# c150_rev_c.net
KiCad netlist of a schematic drawn in EAGLE
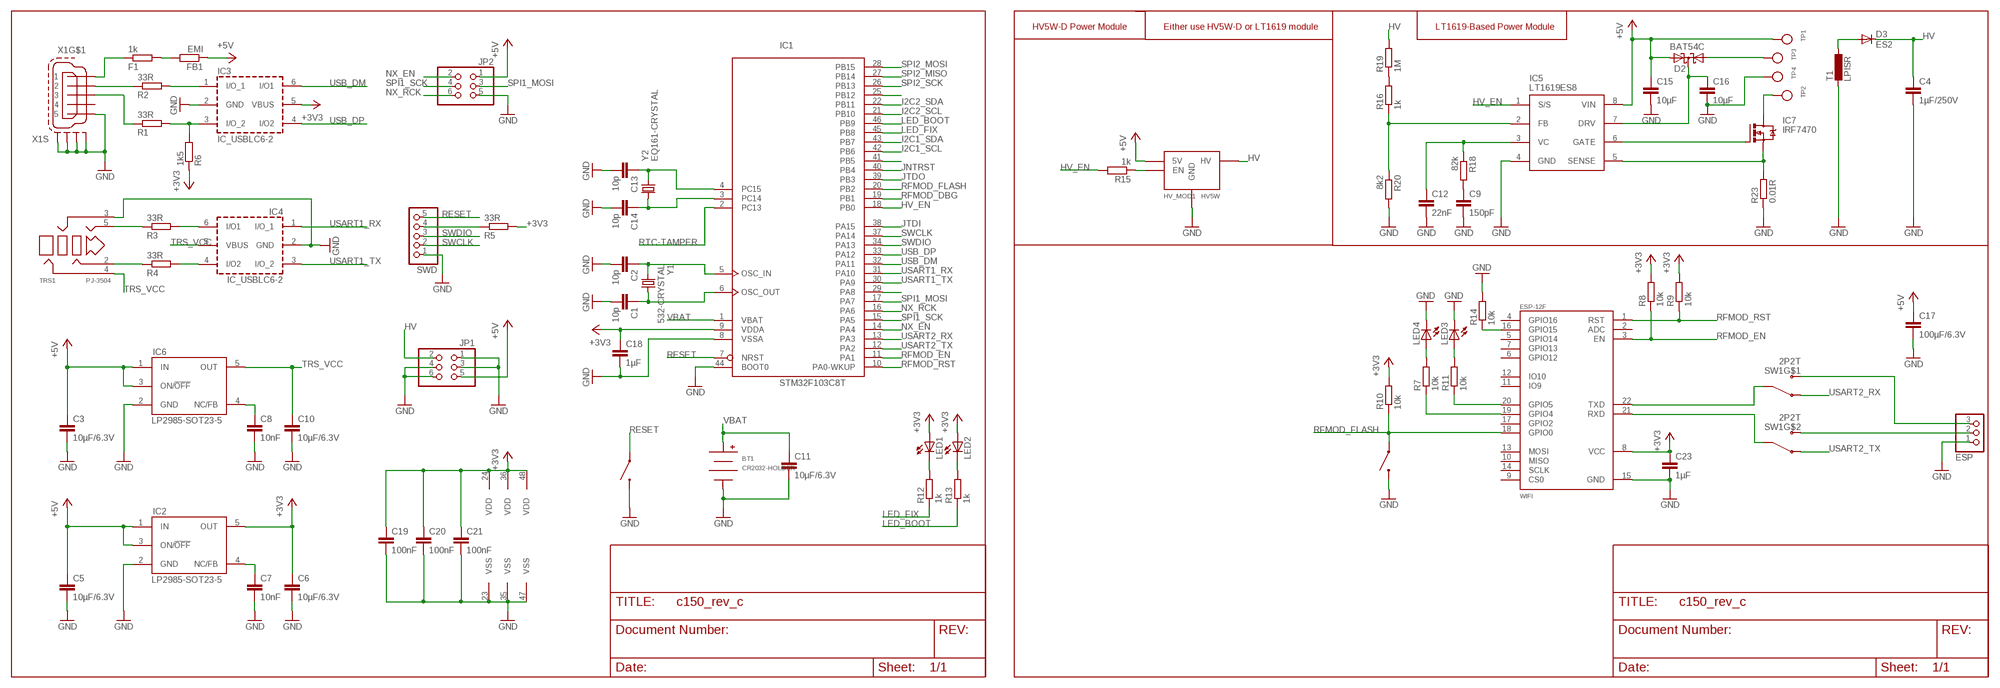
[diagram p0: schematic, sheet 1]

(export (version "E")
  (design (tool "Eeschema 10.0.6"))
  (components
    (comp (ref "BT1")
      (value "CR2032-HOLDER")
      (footprint "eagle-import:CH28-2032LF")
      (libsource (lib "eagle-import") (part "CR2032-HOLDER"))
    )
    (comp (ref "C1")
      (value "10p")
      (footprint "eagle-import:C0603")
      (libsource (lib "eagle-import") (part "C-EUC0603"))
    )
    (comp (ref "C2")
      (value "10p")
      (footprint "eagle-import:C0603")
      (libsource (lib "eagle-import") (part "C-EUC0603"))
    )
    (comp (ref "C3")
      (value "10µF/6.3V")
      (footprint "eagle-import:C0603")
      (libsource (lib "eagle-import") (part "C-EUC0603"))
    )
    (comp (ref "C4")
      (value "1µF/250V")
      (footprint "eagle-import:C2220K")
      (libsource (lib "eagle-import") (part "C-EUC2220K"))
    )
    (comp (ref "C5")
      (value "10µF/6.3V")
      (footprint "eagle-import:C0603")
      (libsource (lib "eagle-import") (part "C-EUC0603"))
    )
    (comp (ref "C6")
      (value "10µF/6.3V")
      (footprint "eagle-import:C0603")
      (libsource (lib "eagle-import") (part "C-EUC0603"))
    )
    (comp (ref "C7")
      (value "10nF")
      (footprint "eagle-import:C0603")
      (libsource (lib "eagle-import") (part "C-EUC0603"))
    )
    (comp (ref "C8")
      (value "10nF")
      (footprint "eagle-import:C0603")
      (libsource (lib "eagle-import") (part "C-EUC0603"))
    )
    (comp (ref "C9")
      (value "150pF")
      (footprint "eagle-import:C0603")
      (libsource (lib "eagle-import") (part "C-EUC0603"))
    )
    (comp (ref "C10")
      (value "10µF/6.3V")
      (footprint "eagle-import:C0603")
      (libsource (lib "eagle-import") (part "C-EUC0603"))
    )
    (comp (ref "C11")
      (value "10µF/6.3V")
      (footprint "eagle-import:C0603")
      (libsource (lib "eagle-import") (part "C-EUC0603"))
    )
    (comp (ref "C12")
      (value "22nF")
      (footprint "eagle-import:C0603")
      (libsource (lib "eagle-import") (part "C-EUC0603"))
    )
    (comp (ref "C13")
      (value "10p")
      (footprint "eagle-import:C0603")
      (libsource (lib "eagle-import") (part "C-EUC0603"))
    )
    (comp (ref "C14")
      (value "10p")
      (footprint "eagle-import:C0603")
      (libsource (lib "eagle-import") (part "C-EUC0603"))
    )
    (comp (ref "C15")
      (value "10µF")
      (footprint "eagle-import:C0603")
      (libsource (lib "eagle-import") (part "C-EUC0603"))
    )
    (comp (ref "C16")
      (value "10µF")
      (footprint "eagle-import:C0603")
      (libsource (lib "eagle-import") (part "C-EUC0603"))
    )
    (comp (ref "C17")
      (value "100µF/6.3V")
      (footprint "eagle-import:C1210")
      (libsource (lib "eagle-import") (part "C-EUC1210"))
    )
    (comp (ref "C18")
      (value "1µF")
      (footprint "eagle-import:C0603")
      (libsource (lib "eagle-import") (part "C-EUC0603"))
    )
    (comp (ref "C19")
      (value "100nF")
      (footprint "eagle-import:C0603")
      (libsource (lib "eagle-import") (part "C-EUC0603"))
    )
    (comp (ref "C20")
      (value "100nF")
      (footprint "eagle-import:C0603")
      (libsource (lib "eagle-import") (part "C-EUC0603"))
    )
    (comp (ref "C21")
      (value "100nF")
      (footprint "eagle-import:C0603")
      (libsource (lib "eagle-import") (part "C-EUC0603"))
    )
    (comp (ref "C23")
      (value "1µF")
      (footprint "eagle-import:C0603")
      (libsource (lib "eagle-import") (part "C-EUC0603"))
    )
    (comp (ref "D2")
      (value "BAT54C")
      (footprint "eagle-import:SOT23")
      (libsource (lib "eagle-import") (part "BAT54C"))
    )
    (comp (ref "D3")
      (value "ES2")
      (footprint "eagle-import:DO-214AA")
      (libsource (lib "eagle-import") (part "ES2"))
    )
    (comp (ref "ESP")
      (value "HEADER-1X3ROUND")
      (footprint "eagle-import:1X03_ROUND")
      (libsource (lib "eagle-import") (part "HEADER-1X3ROUND"))
    )
    (comp (ref "F1")
      (value "1k")
      (footprint "eagle-import:R0603")
      (libsource (lib "eagle-import") (part "R-EU_R0603"))
    )
    (comp (ref "FB1")
      (value "EMI")
      (footprint "eagle-import:R0603")
      (libsource (lib "eagle-import") (part "R-EU_R0603"))
    )
    (comp (ref "FLASH")
      (value "TACT-SWITCH-40-40")
      (footprint "eagle-import:40-40")
      (libsource (lib "eagle-import") (part "TACT-SWITCH-40-40"))
    )
    (comp (ref "HV_MOD1")
      (value "HV5W")
      (footprint "eagle-import:HV5W-D")
      (libsource (lib "eagle-import") (part "HV5W"))
    )
    (comp (ref "IC1")
      (value "STM32F103C8T")
      (footprint "eagle-import:LQFP48")
      (libsource (lib "eagle-import") (part "STM32F103CT8"))
    )
    (comp (ref "IC2")
      (value "LP2985-SOT23-5")
      (footprint "eagle-import:SOT23-5")
      (libsource (lib "eagle-import") (part "LP2985-SOT23-5"))
    )
    (comp (ref "IC3")
      (value "IC_USBLC6-2")
      (footprint "eagle-import:SOT-23-6L")
      (libsource (lib "eagle-import") (part "IC_USBLC6-2"))
    )
    (comp (ref "IC4")
      (value "IC_USBLC6-2")
      (footprint "eagle-import:SOT-23-6L")
      (libsource (lib "eagle-import") (part "IC_USBLC6-2"))
    )
    (comp (ref "IC5")
      (value "LT1619ES8")
      (footprint "eagle-import:SO8")
      (libsource (lib "eagle-import") (part "LT1619ES8"))
    )
    (comp (ref "IC6")
      (value "LP2985-SOT23-5")
      (footprint "eagle-import:SOT23-5")
      (libsource (lib "eagle-import") (part "LP2985-SOT23-5"))
    )
    (comp (ref "IC7")
      (value "IRF7470")
      (footprint "eagle-import:SO8")
      (libsource (lib "eagle-import") (part "IRF7470"))
    )
    (comp (ref "ISP")
      (value "TACT-SWITCH-40-40")
      (footprint "eagle-import:40-40")
      (libsource (lib "eagle-import") (part "TACT-SWITCH-40-40"))
    )
    (comp (ref "JP1")
      (value "PINHD-2X3_2.54-SMD")
      (footprint "eagle-import:2X03SMD")
      (libsource (lib "eagle-import") (part "PINHD-2X3_2.54-SMD"))
    )
    (comp (ref "JP2")
      (value "PINHD-2X3_2.54-SMD")
      (footprint "eagle-import:2X03SMD")
      (libsource (lib "eagle-import") (part "PINHD-2X3_2.54-SMD"))
    )
    (comp (ref "LED1")
      (value "LEDCHIP-LED0603")
      (footprint "eagle-import:CHIP-LED0603")
      (libsource (lib "eagle-import") (part "LEDCHIP-LED0603"))
    )
    (comp (ref "LED2")
      (value "LEDCHIP-LED0603")
      (footprint "eagle-import:CHIP-LED0603")
      (libsource (lib "eagle-import") (part "LEDCHIP-LED0603"))
    )
    (comp (ref "LED3")
      (value "LEDCHIP-LED0603")
      (footprint "eagle-import:CHIP-LED0603")
      (libsource (lib "eagle-import") (part "LEDCHIP-LED0603"))
    )
    (comp (ref "LED4")
      (value "LEDCHIP-LED0603")
      (footprint "eagle-import:CHIP-LED0603")
      (libsource (lib "eagle-import") (part "LEDCHIP-LED0603"))
    )
    (comp (ref "R1")
      (value "33R")
      (footprint "eagle-import:R0603")
      (libsource (lib "eagle-import") (part "R-EU_R0603"))
    )
    (comp (ref "R2")
      (value "33R")
      (footprint "eagle-import:R0603")
      (libsource (lib "eagle-import") (part "R-EU_R0603"))
    )
    (comp (ref "R3")
      (value "33R")
      (footprint "eagle-import:R0603")
      (libsource (lib "eagle-import") (part "R-EU_R0603"))
    )
    (comp (ref "R4")
      (value "33R")
      (footprint "eagle-import:R0603")
      (libsource (lib "eagle-import") (part "R-EU_R0603"))
    )
    (comp (ref "R5")
      (value "33R")
      (footprint "eagle-import:R0603")
      (libsource (lib "eagle-import") (part "R-EU_R0603"))
    )
    (comp (ref "R6")
      (value "1k5")
      (footprint "eagle-import:R0603")
      (libsource (lib "eagle-import") (part "R-EU_R0603"))
    )
    (comp (ref "R7")
      (value "10k")
      (footprint "eagle-import:R0603")
      (libsource (lib "eagle-import") (part "R-EU_R0603"))
    )
    (comp (ref "R8")
      (value "10k")
      (footprint "eagle-import:R0603")
      (libsource (lib "eagle-import") (part "R-EU_R0603"))
    )
    (comp (ref "R9")
      (value "10k")
      (footprint "eagle-import:R0603")
      (libsource (lib "eagle-import") (part "R-EU_R0603"))
    )
    (comp (ref "R10")
      (value "10k")
      (footprint "eagle-import:R0603")
      (libsource (lib "eagle-import") (part "R-EU_R0603"))
    )
    (comp (ref "R11")
      (value "10k")
      (footprint "eagle-import:R0603")
      (libsource (lib "eagle-import") (part "R-EU_R0603"))
    )
    (comp (ref "R12")
      (value "1k")
      (footprint "eagle-import:R0603")
      (libsource (lib "eagle-import") (part "R-EU_R0603"))
    )
    (comp (ref "R13")
      (value "1k")
      (footprint "eagle-import:R0603")
      (libsource (lib "eagle-import") (part "R-EU_R0603"))
    )
    (comp (ref "R14")
      (value "10k")
      (footprint "eagle-import:R0603")
      (libsource (lib "eagle-import") (part "R-EU_R0603"))
    )
    (comp (ref "R15")
      (value "1k")
      (footprint "eagle-import:R1206")
      (libsource (lib "eagle-import") (part "R-EU_R1206"))
    )
    (comp (ref "R16")
      (value "1k")
      (footprint "eagle-import:R0603")
      (libsource (lib "eagle-import") (part "R-EU_R0603"))
    )
    (comp (ref "R18")
      (value "82k")
      (footprint "eagle-import:R0603")
      (libsource (lib "eagle-import") (part "R-EU_R0603"))
    )
    (comp (ref "R19")
      (value "1M")
      (footprint "eagle-import:M1206")
      (libsource (lib "eagle-import") (part "R-EU_M1206"))
    )
    (comp (ref "R20")
      (value "8k2")
      (footprint "eagle-import:R0603")
      (libsource (lib "eagle-import") (part "R-EU_R0603"))
    )
    (comp (ref "R23")
      (value "0.01R")
      (footprint "eagle-import:R1206")
      (libsource (lib "eagle-import") (part "R-EU_R1206"))
    )
    (comp (ref "SW1")
      (value "2P2T")
      (footprint "eagle-import:MSS22D18")
      (libsource (lib "eagle-import") (part "2P2T"))
    )
    (comp (ref "SWD")
      (value "HEADER-1X5ROUND")
      (footprint "eagle-import:1X05_ROUND")
      (libsource (lib "eagle-import") (part "HEADER-1X5ROUND"))
    )
    (comp (ref "T1")
      (value "LPISR")
      (footprint "eagle-import:PISR")
      (libsource (lib "eagle-import") (part "LPISR"))
    )
    (comp (ref "TP1")
      (value "TESTPOINTROUND2MM")
      (footprint "eagle-import:TESTPOINT_ROUND_2MM")
      (libsource (lib "eagle-import") (part "TESTPOINTROUND2MM"))
    )
    (comp (ref "TP2")
      (value "TESTPOINTROUND2MM")
      (footprint "eagle-import:TESTPOINT_ROUND_2MM")
      (libsource (lib "eagle-import") (part "TESTPOINTROUND2MM"))
    )
    (comp (ref "TP3")
      (value "TESTPOINTROUND2MM")
      (footprint "eagle-import:TESTPOINT_ROUND_2MM")
      (libsource (lib "eagle-import") (part "TESTPOINTROUND2MM"))
    )
    (comp (ref "TP4")
      (value "TESTPOINTROUND2MM")
      (footprint "eagle-import:TESTPOINT_ROUND_2MM")
      (libsource (lib "eagle-import") (part "TESTPOINTROUND2MM"))
    )
    (comp (ref "TRS1")
      (value "PJ-3504")
      (footprint "eagle-import:YD-PJ-3504")
      (libsource (lib "eagle-import") (part "PJ-3504"))
    )
    (comp (ref "WIFI")
      (value "ESP-12F")
      (footprint "eagle-import:ESP-12F")
      (libsource (lib "eagle-import") (part "ESP-12F"))
    )
    (comp (ref "X1")
      (value "MINI-USB-SCHIELD-32005-201")
      (footprint "eagle-import:32005-201")
      (libsource (lib "eagle-import") (part "MINI-USB-SCHIELD-32005-201"))
    )
    (comp (ref "Y1")
      (value "532-CRYSTAL")
      (footprint "eagle-import:2PIN50X32")
      (libsource (lib "eagle-import") (part "532-CRYSTAL"))
    )
    (comp (ref "Y2")
      (value "EQ161-CRYSTAL")
      (footprint "eagle-import:EQ161")
      (libsource (lib "eagle-import") (part "EQ161-CRYSTAL"))
    )
  )
  (nets
    (net (code "1") (name "+3V3") (class "Default")
      (node (ref "C18") (pin "1") (pinfunction "1_1") (pintype "passive"))
      (node (ref "C19") (pin "1") (pinfunction "1_1") (pintype "passive"))
      (node (ref "C20") (pin "1") (pinfunction "1_1") (pintype "passive"))
      (node (ref "C21") (pin "1") (pinfunction "1_1") (pintype "passive"))
      (node (ref "C23") (pin "1") (pinfunction "1_1") (pintype "passive"))
      (node (ref "C6") (pin "1") (pinfunction "1_1") (pintype "passive"))
      (node (ref "IC1") (pin "24") (pinfunction "VDD_24") (pintype "power_in"))
      (node (ref "IC1") (pin "36") (pinfunction "VDD_36") (pintype "power_in"))
      (node (ref "IC1") (pin "48") (pinfunction "VDD_48") (pintype "power_in"))
      (node (ref "IC1") (pin "9") (pinfunction "VDDA_9") (pintype "power_in"))
      (node (ref "IC2") (pin "5") (pinfunction "OUT_5") (pintype "bidirectional"))
      (node (ref "IC3") (pin "5") (pinfunction "VBUS_5") (pintype "bidirectional"))
      (node (ref "LED1") (pin "A") (pinfunction "A_A") (pintype "passive"))
      (node (ref "LED2") (pin "A") (pinfunction "A_A") (pintype "passive"))
      (node (ref "R10") (pin "2") (pinfunction "2_2") (pintype "passive"))
      (node (ref "R5") (pin "2") (pinfunction "2_2") (pintype "passive"))
      (node (ref "R6") (pin "1") (pinfunction "1_1") (pintype "passive"))
      (node (ref "R8") (pin "2") (pinfunction "2_2") (pintype "passive"))
      (node (ref "R9") (pin "2") (pinfunction "2_2") (pintype "passive"))
      (node (ref "WIFI") (pin "8") (pinfunction "VCC_8") (pintype "bidirectional"))
    )
    (net (code "2") (name "+5V") (class "Default")
      (node (ref "C15") (pin "1") (pinfunction "1_1") (pintype "passive"))
      (node (ref "C17") (pin "1") (pinfunction "1_1") (pintype "passive"))
      (node (ref "C3") (pin "1") (pinfunction "1_1") (pintype "passive"))
      (node (ref "C5") (pin "1") (pinfunction "1_1") (pintype "passive"))
      (node (ref "D2") (pin "2") (pinfunction "A2_2") (pintype "passive"))
      (node (ref "FB1") (pin "1") (pinfunction "1_1") (pintype "passive"))
      (node (ref "HV_MOD1") (pin "+5V") (pinfunction "5V_+5V") (pintype "bidirectional"))
      (node (ref "IC2") (pin "1") (pinfunction "IN_1") (pintype "bidirectional"))
      (node (ref "IC2") (pin "3") (pinfunction "ON/~{OFF}_3") (pintype "bidirectional"))
      (node (ref "IC5") (pin "8") (pinfunction "VIN_8") (pintype "bidirectional"))
      (node (ref "IC6") (pin "1") (pinfunction "IN_1") (pintype "bidirectional"))
      (node (ref "IC6") (pin "3") (pinfunction "ON/~{OFF}_3") (pintype "bidirectional"))
      (node (ref "JP1") (pin "5") (pinfunction "5_5") (pintype "passive"))
      (node (ref "JP2") (pin "1") (pinfunction "1_1") (pintype "passive"))
      (node (ref "TP1") (pin "P$1") (pinfunction "P$1_P$1") (pintype "bidirectional"))
    )
    (net (code "3") (name "/HV") (class "Default")
      (node (ref "C4") (pin "1") (pinfunction "1_1") (pintype "passive"))
      (node (ref "D3") (pin "C") (pinfunction "C_C") (pintype "passive"))
      (node (ref "HV_MOD1") (pin "HV") (pinfunction "HV_HV") (pintype "bidirectional"))
      (node (ref "JP1") (pin "2") (pinfunction "2_2") (pintype "passive"))
      (node (ref "R19") (pin "2") (pinfunction "2_2") (pintype "passive"))
    )
    (net (code "4") (name "/HV_EN") (class "Default")
      (node (ref "IC1") (pin "18") (pinfunction "PB0_18") (pintype "bidirectional"))
      (node (ref "IC5") (pin "1") (pinfunction "S/S_1") (pintype "bidirectional"))
      (node (ref "R15") (pin "2") (pinfunction "2_2") (pintype "passive"))
    )
    (net (code "5") (name "/I2C1_SCL") (class "Default")
      (node (ref "IC1") (pin "42") (pinfunction "PB6_42") (pintype "bidirectional"))
    )
    (net (code "6") (name "/I2C1_SDA") (class "Default")
      (node (ref "IC1") (pin "43") (pinfunction "PB7_43") (pintype "bidirectional"))
    )
    (net (code "7") (name "/I2C2_SCL") (class "Default")
      (node (ref "IC1") (pin "21") (pinfunction "PB10_21") (pintype "bidirectional"))
    )
    (net (code "8") (name "/I2C2_SDA") (class "Default")
      (node (ref "IC1") (pin "22") (pinfunction "PB11_22") (pintype "bidirectional"))
    )
    (net (code "9") (name "/JNTRST") (class "Default")
      (node (ref "IC1") (pin "40") (pinfunction "PB4_40") (pintype "bidirectional"))
    )
    (net (code "10") (name "/JTDI") (class "Default")
      (node (ref "IC1") (pin "38") (pinfunction "PA15_38") (pintype "bidirectional"))
    )
    (net (code "11") (name "/JTDO") (class "Default")
      (node (ref "IC1") (pin "39") (pinfunction "PB3_39") (pintype "bidirectional"))
    )
    (net (code "12") (name "/LED_BOOT") (class "Default")
      (node (ref "IC1") (pin "46") (pinfunction "PB9_46") (pintype "bidirectional"))
      (node (ref "R13") (pin "1") (pinfunction "1_1") (pintype "passive"))
    )
    (net (code "13") (name "/LED_FIX") (class "Default")
      (node (ref "IC1") (pin "45") (pinfunction "PB8_45") (pintype "bidirectional"))
      (node (ref "R12") (pin "1") (pinfunction "1_1") (pintype "passive"))
    )
    (net (code "14") (name "/NX_EN") (class "Default")
      (node (ref "IC1") (pin "14") (pinfunction "PA4_14") (pintype "bidirectional"))
      (node (ref "JP2") (pin "2") (pinfunction "2_2") (pintype "passive"))
    )
    (net (code "15") (name "/NX_RCK") (class "Default")
      (node (ref "IC1") (pin "16") (pinfunction "PA6_16") (pintype "bidirectional"))
      (node (ref "JP2") (pin "6") (pinfunction "6_6") (pintype "passive"))
    )
    (net (code "16") (name "/RESET") (class "Default")
      (node (ref "IC1") (pin "7") (pinfunction "NRST_7") (pintype "bidirectional"))
      (node (ref "ISP") (pin "3") (pinfunction "P$2_3") (pintype "bidirectional"))
      (node (ref "ISP") (pin "4") (pinfunction "P$2_4") (pintype "bidirectional"))
      (node (ref "SWD") (pin "5") (pinfunction "5_5") (pintype "passive"))
    )
    (net (code "17") (name "/RFMOD_DBG") (class "Default")
      (node (ref "IC1") (pin "19") (pinfunction "PB1_19") (pintype "bidirectional"))
    )
    (net (code "18") (name "/RFMOD_EN") (class "Default")
      (node (ref "IC1") (pin "11") (pinfunction "PA1_11") (pintype "bidirectional"))
      (node (ref "R8") (pin "1") (pinfunction "1_1") (pintype "passive"))
      (node (ref "WIFI") (pin "3") (pinfunction "EN_3") (pintype "bidirectional"))
    )
    (net (code "19") (name "/RFMOD_FLASH") (class "Default")
      (node (ref "FLASH") (pin "3") (pinfunction "P$2_3") (pintype "bidirectional"))
      (node (ref "FLASH") (pin "4") (pinfunction "P$2_4") (pintype "bidirectional"))
      (node (ref "IC1") (pin "20") (pinfunction "PB2_20") (pintype "bidirectional"))
      (node (ref "R10") (pin "1") (pinfunction "1_1") (pintype "passive"))
      (node (ref "WIFI") (pin "18") (pinfunction "GPIO0_18") (pintype "bidirectional"))
    )
    (net (code "20") (name "/RFMOD_RST") (class "Default")
      (node (ref "IC1") (pin "10") (pinfunction "PA0-WKUP_10") (pintype "bidirectional"))
      (node (ref "R9") (pin "1") (pinfunction "1_1") (pintype "passive"))
      (node (ref "WIFI") (pin "1") (pinfunction "RST_1") (pintype "bidirectional"))
    )
    (net (code "21") (name "/RTC-TAMPER") (class "Default")
      (node (ref "IC1") (pin "2") (pinfunction "PC13_2") (pintype "bidirectional"))
    )
    (net (code "22") (name "/SPI1_MOSI") (class "Default")
      (node (ref "IC1") (pin "17") (pinfunction "PA7_17") (pintype "bidirectional"))
      (node (ref "JP2") (pin "3") (pinfunction "3_3") (pintype "passive"))
    )
    (net (code "23") (name "/SPI1_SCK") (class "Default")
      (node (ref "IC1") (pin "15") (pinfunction "PA5_15") (pintype "bidirectional"))
      (node (ref "JP2") (pin "4") (pinfunction "4_4") (pintype "passive"))
    )
    (net (code "24") (name "/SPI2_MISO") (class "Default")
      (node (ref "IC1") (pin "27") (pinfunction "PB14_27") (pintype "bidirectional"))
    )
    (net (code "25") (name "/SPI2_MOSI") (class "Default")
      (node (ref "IC1") (pin "28") (pinfunction "PB15_28") (pintype "bidirectional"))
    )
    (net (code "26") (name "/SPI2_SCK") (class "Default")
      (node (ref "IC1") (pin "26") (pinfunction "PB13_26") (pintype "bidirectional"))
    )
    (net (code "27") (name "/SWCLK") (class "Default")
      (node (ref "IC1") (pin "37") (pinfunction "PA14_37") (pintype "bidirectional"))
      (node (ref "SWD") (pin "2") (pinfunction "2_2") (pintype "passive"))
    )
    (net (code "28") (name "/SWDIO") (class "Default")
      (node (ref "IC1") (pin "34") (pinfunction "PA13_34") (pintype "bidirectional"))
      (node (ref "SWD") (pin "3") (pinfunction "3_3") (pintype "passive"))
    )
    (net (code "29") (name "/TRS_VCC") (class "Default")
      (node (ref "C10") (pin "1") (pinfunction "1_1") (pintype "passive"))
      (node (ref "IC4") (pin "5") (pinfunction "VBUS_5") (pintype "bidirectional"))
      (node (ref "IC6") (pin "5") (pinfunction "OUT_5") (pintype "bidirectional"))
      (node (ref "TRS1") (pin "4") (pinfunction "4_4") (pintype "bidirectional"))
    )
    (net (code "30") (name "/USART1_RX") (class "Default")
      (node (ref "IC1") (pin "31") (pinfunction "PA10_31") (pintype "bidirectional"))
      (node (ref "IC4") (pin "1") (pinfunction "I/O_1_1") (pintype "bidirectional"))
    )
    (net (code "31") (name "/USART1_TX") (class "Default")
      (node (ref "IC1") (pin "30") (pinfunction "PA9_30") (pintype "bidirectional"))
      (node (ref "IC4") (pin "3") (pinfunction "I/O_2_3") (pintype "bidirectional"))
    )
    (net (code "32") (name "/USART2_RX") (class "Default")
      (node (ref "IC1") (pin "13") (pinfunction "PA3_13") (pintype "bidirectional"))
      (node (ref "SW1") (pin "A1") (pinfunction "A_A1") (pintype "bidirectional"))
    )
    (net (code "33") (name "/USART2_TX") (class "Default")
      (node (ref "IC1") (pin "12") (pinfunction "PA2_12") (pintype "bidirectional"))
      (node (ref "SW1") (pin "A2") (pinfunction "A_A2") (pintype "bidirectional"))
    )
    (net (code "34") (name "/USB_DM") (class "Default")
      (node (ref "IC1") (pin "32") (pinfunction "PA11_32") (pintype "bidirectional"))
      (node (ref "IC3") (pin "6") (pinfunction "I/O1_6") (pintype "bidirectional"))
    )
    (net (code "35") (name "/USB_DP") (class "Default")
      (node (ref "IC1") (pin "33") (pinfunction "PA12_33") (pintype "bidirectional"))
      (node (ref "IC3") (pin "4") (pinfunction "I/O2_4") (pintype "bidirectional"))
    )
    (net (code "36") (name "/VBAT") (class "Default")
      (node (ref "BT1") (pin "POS") (pinfunction "POS_POS") (pintype "bidirectional"))
      (node (ref "C11") (pin "1") (pinfunction "1_1") (pintype "passive"))
      (node (ref "IC1") (pin "1") (pinfunction "VBAT_1") (pintype "power_in"))
    )
    (net (code "37") (name "GND") (class "Default")
      (node (ref "BT1") (pin "NEG") (pinfunction "NEG_NEG") (pintype "bidirectional"))
      (node (ref "C1") (pin "2") (pinfunction "2_2") (pintype "passive"))
      (node (ref "C10") (pin "2") (pinfunction "2_2") (pintype "passive"))
      (node (ref "C11") (pin "2") (pinfunction "2_2") (pintype "passive"))
      (node (ref "C12") (pin "2") (pinfunction "2_2") (pintype "passive"))
      (node (ref "C13") (pin "2") (pinfunction "2_2") (pintype "passive"))
      (node (ref "C14") (pin "2") (pinfunction "2_2") (pintype "passive"))
      (node (ref "C15") (pin "2") (pinfunction "2_2") (pintype "passive"))
      (node (ref "C16") (pin "2") (pinfunction "2_2") (pintype "passive"))
      (node (ref "C17") (pin "2") (pinfunction "2_2") (pintype "passive"))
      (node (ref "C18") (pin "2") (pinfunction "2_2") (pintype "passive"))
      (node (ref "C19") (pin "2") (pinfunction "2_2") (pintype "passive"))
      (node (ref "C2") (pin "2") (pinfunction "2_2") (pintype "passive"))
      (node (ref "C20") (pin "2") (pinfunction "2_2") (pintype "passive"))
      (node (ref "C21") (pin "2") (pinfunction "2_2") (pintype "passive"))
      (node (ref "C23") (pin "2") (pinfunction "2_2") (pintype "passive"))
      (node (ref "C3") (pin "2") (pinfunction "2_2") (pintype "passive"))
      (node (ref "C4") (pin "2") (pinfunction "2_2") (pintype "passive"))
      (node (ref "C5") (pin "2") (pinfunction "2_2") (pintype "passive"))
      (node (ref "C6") (pin "2") (pinfunction "2_2") (pintype "passive"))
      (node (ref "C7") (pin "2") (pinfunction "2_2") (pintype "passive"))
      (node (ref "C8") (pin "2") (pinfunction "2_2") (pintype "passive"))
      (node (ref "C9") (pin "2") (pinfunction "2_2") (pintype "passive"))
      (node (ref "ESP") (pin "1") (pinfunction "1_1") (pintype "passive"))
      (node (ref "FLASH") (pin "1") (pinfunction "P$1_1") (pintype "bidirectional"))
      (node (ref "FLASH") (pin "2") (pinfunction "P$1_2") (pintype "bidirectional"))
      (node (ref "HV_MOD1") (pin "GND1") (pinfunction "GND_GND1") (pintype "bidirectional"))
      (node (ref "HV_MOD1") (pin "GND2") (pinfunction "GND_GND2") (pintype "bidirectional"))
      (node (ref "HV_MOD1") (pin "GND3") (pinfunction "GND_GND3") (pintype "bidirectional"))
      (node (ref "IC1") (pin "23") (pinfunction "VSS_23") (pintype "power_in"))
      (node (ref "IC1") (pin "35") (pinfunction "VSS_35") (pintype "power_in"))
      (node (ref "IC1") (pin "44") (pinfunction "BOOT0_44") (pintype "input"))
      (node (ref "IC1") (pin "47") (pinfunction "VSS_47") (pintype "power_in"))
      (node (ref "IC1") (pin "8") (pinfunction "VSSA_8") (pintype "power_in"))
      (node (ref "IC2") (pin "2") (pinfunction "GND_2") (pintype "bidirectional"))
      (node (ref "IC3") (pin "2") (pinfunction "GND_2") (pintype "bidirectional"))
      (node (ref "IC4") (pin "2") (pinfunction "GND_2") (pintype "bidirectional"))
      (node (ref "IC5") (pin "4") (pinfunction "GND_4") (pintype "bidirectional"))
      (node (ref "IC6") (pin "2") (pinfunction "GND_2") (pintype "bidirectional"))
      (node (ref "ISP") (pin "1") (pinfunction "P$1_1") (pintype "bidirectional"))
      (node (ref "ISP") (pin "2") (pinfunction "P$1_2") (pintype "bidirectional"))
      (node (ref "JP1") (pin "1") (pinfunction "1_1") (pintype "passive"))
      (node (ref "JP1") (pin "3") (pinfunction "3_3") (pintype "passive"))
      (node (ref "JP1") (pin "4") (pinfunction "4_4") (pintype "passive"))
      (node (ref "JP1") (pin "6") (pinfunction "6_6") (pintype "passive"))
      (node (ref "JP2") (pin "5") (pinfunction "5_5") (pintype "passive"))
      (node (ref "LED3") (pin "C") (pinfunction "C_C") (pintype "passive"))
      (node (ref "LED4") (pin "C") (pinfunction "C_C") (pintype "passive"))
      (node (ref "R14") (pin "2") (pinfunction "2_2") (pintype "passive"))
      (node (ref "R20") (pin "2") (pinfunction "2_2") (pintype "passive"))
      (node (ref "R23") (pin "1") (pinfunction "1_1") (pintype "passive"))
      (node (ref "SWD") (pin "1") (pinfunction "1_1") (pintype "passive"))
      (node (ref "T1") (pin "P$2") (pinfunction "2_P$2") (pintype "passive"))
      (node (ref "TP4") (pin "P$1") (pinfunction "P$1_P$1") (pintype "bidirectional"))
      (node (ref "TRS1") (pin "3") (pinfunction "3_3") (pintype "bidirectional"))
      (node (ref "WIFI") (pin "15") (pinfunction "GND_15") (pintype "bidirectional"))
      (node (ref "X1") (pin "5") (pinfunction "5_5") (pintype "passive"))
      (node (ref "X1") (pin "M1") (pinfunction "S1_M1") (pintype "passive"))
      (node (ref "X1") (pin "M2") (pinfunction "S2_M2") (pintype "passive"))
      (node (ref "X1") (pin "M3") (pinfunction "S3_M3") (pintype "passive"))
      (node (ref "X1") (pin "M4") (pinfunction "S4_M4") (pintype "passive"))
    )
    (net (code "38") (name "Net-(C9-Pad1)") (class "Default")
      (node (ref "C9") (pin "1") (pinfunction "1_1") (pintype "passive"))
      (node (ref "R18") (pin "2") (pinfunction "2_2") (pintype "passive"))
    )
    (net (code "39") (name "Net-(D2-A1)") (class "Default")
      (node (ref "D2") (pin "1") (pinfunction "A1_1") (pintype "passive"))
      (node (ref "TP3") (pin "P$1") (pinfunction "P$1_P$1") (pintype "bidirectional"))
    )
    (net (code "40") (name "Net-(D2-CC)") (class "Default")
      (node (ref "C16") (pin "1") (pinfunction "1_1") (pintype "passive"))
      (node (ref "D2") (pin "3") (pinfunction "CC_3") (pintype "passive"))
      (node (ref "IC5") (pin "7") (pinfunction "DRV_7") (pintype "bidirectional"))
    )
    (net (code "41") (name "Net-(F1-Pad1)") (class "Default")
      (node (ref "F1") (pin "1") (pinfunction "1_1") (pintype "passive"))
      (node (ref "X1") (pin "1") (pinfunction "1_1") (pintype "passive"))
    )
    (net (code "42") (name "Net-(F1-Pad2)") (class "Default")
      (node (ref "F1") (pin "2") (pinfunction "2_2") (pintype "passive"))
      (node (ref "FB1") (pin "2") (pinfunction "2_2") (pintype "passive"))
    )
    (net (code "43") (name "Net-(HV_MOD1-PadEN)") (class "Default")
      (node (ref "HV_MOD1") (pin "EN") (pinfunction "EN_EN") (pintype "bidirectional"))
      (node (ref "R15") (pin "1") (pinfunction "1_1") (pintype "passive"))
    )
    (net (code "44") (name "Net-(IC1A-OSC_IN)") (class "Default")
      (node (ref "C2") (pin "1") (pinfunction "1_1") (pintype "passive"))
      (node (ref "IC1") (pin "5") (pinfunction "OSC_IN_5") (pintype "bidirectional"))
      (node (ref "Y1") (pin "P$2") (pinfunction "2_P$2") (pintype "passive"))
    )
    (net (code "45") (name "Net-(IC1A-OSC_OUT)") (class "Default")
      (node (ref "C1") (pin "1") (pinfunction "1_1") (pintype "passive"))
      (node (ref "IC1") (pin "6") (pinfunction "OSC_OUT_6") (pintype "bidirectional"))
      (node (ref "Y1") (pin "P$1") (pinfunction "1_P$1") (pintype "passive"))
    )
    (net (code "46") (name "Net-(IC1A-PC14)") (class "Default")
      (node (ref "C14") (pin "1") (pinfunction "1_1") (pintype "passive"))
      (node (ref "IC1") (pin "3") (pinfunction "PC14_3") (pintype "bidirectional"))
      (node (ref "Y2") (pin "P$2") (pinfunction "2_P$2") (pintype "passive"))
    )
    (net (code "47") (name "Net-(IC1A-PC15)") (class "Default")
      (node (ref "C13") (pin "1") (pinfunction "1_1") (pintype "passive"))
      (node (ref "IC1") (pin "4") (pinfunction "PC15_4") (pintype "bidirectional"))
      (node (ref "Y2") (pin "P$1") (pinfunction "1_P$1") (pintype "passive"))
    )
    (net (code "48") (name "Net-(IC2-NC{slash}FB)") (class "Default")
      (node (ref "C7") (pin "1") (pinfunction "1_1") (pintype "passive"))
      (node (ref "IC2") (pin "4") (pinfunction "NC/FB_4") (pintype "bidirectional"))
    )
    (net (code "49") (name "Net-(IC3-I{slash}O_1)") (class "Default")
      (node (ref "IC3") (pin "1") (pinfunction "I/O_1_1") (pintype "bidirectional"))
      (node (ref "R2") (pin "2") (pinfunction "2_2") (pintype "passive"))
    )
    (net (code "50") (name "Net-(IC3-I{slash}O_2)") (class "Default")
      (node (ref "IC3") (pin "3") (pinfunction "I/O_2_3") (pintype "bidirectional"))
      (node (ref "R1") (pin "2") (pinfunction "2_2") (pintype "passive"))
      (node (ref "R6") (pin "2") (pinfunction "2_2") (pintype "passive"))
    )
    (net (code "51") (name "Net-(IC4-I{slash}O1)") (class "Default")
      (node (ref "IC4") (pin "6") (pinfunction "I/O1_6") (pintype "bidirectional"))
      (node (ref "R3") (pin "2") (pinfunction "2_2") (pintype "passive"))
    )
    (net (code "52") (name "Net-(IC4-I{slash}O2)") (class "Default")
      (node (ref "IC4") (pin "4") (pinfunction "I/O2_4") (pintype "bidirectional"))
      (node (ref "R4") (pin "2") (pinfunction "2_2") (pintype "passive"))
    )
    (net (code "53") (name "Net-(IC5-FB)") (class "Default")
      (node (ref "IC5") (pin "2") (pinfunction "FB_2") (pintype "bidirectional"))
      (node (ref "R16") (pin "1") (pinfunction "1_1") (pintype "passive"))
      (node (ref "R20") (pin "1") (pinfunction "1_1") (pintype "passive"))
    )
    (net (code "54") (name "Net-(IC5-GATE)") (class "Default")
      (node (ref "IC5") (pin "6") (pinfunction "GATE_6") (pintype "bidirectional"))
      (node (ref "IC7") (pin "4") (pinfunction "G_4") (pintype "passive"))
    )
    (net (code "55") (name "Net-(IC5-SENSE)") (class "Default")
      (node (ref "IC5") (pin "5") (pinfunction "SENSE_5") (pintype "bidirectional"))
      (node (ref "IC7") (pin "1") (pinfunction "S_1") (pintype "passive"))
      (node (ref "IC7") (pin "2") (pinfunction "S_2") (pintype "passive"))
      (node (ref "IC7") (pin "3") (pinfunction "S_3") (pintype "passive"))
      (node (ref "R23") (pin "2") (pinfunction "2_2") (pintype "passive"))
    )
    (net (code "56") (name "Net-(IC5-VC)") (class "Default")
      (node (ref "C12") (pin "1") (pinfunction "1_1") (pintype "passive"))
      (node (ref "IC5") (pin "3") (pinfunction "VC_3") (pintype "bidirectional"))
      (node (ref "R18") (pin "1") (pinfunction "1_1") (pintype "passive"))
    )
    (net (code "57") (name "Net-(IC6-NC{slash}FB)") (class "Default")
      (node (ref "C8") (pin "1") (pinfunction "1_1") (pintype "passive"))
      (node (ref "IC6") (pin "4") (pinfunction "NC/FB_4") (pintype "bidirectional"))
    )
    (net (code "58") (name "Net-(IC7-D-Pad5)") (class "Default")
      (node (ref "IC7") (pin "5") (pinfunction "D_5") (pintype "passive"))
      (node (ref "IC7") (pin "6") (pinfunction "D_6") (pintype "passive"))
      (node (ref "IC7") (pin "7") (pinfunction "D_7") (pintype "passive"))
      (node (ref "IC7") (pin "8") (pinfunction "D_8") (pintype "passive"))
      (node (ref "TP2") (pin "P$1") (pinfunction "P$1_P$1") (pintype "bidirectional"))
    )
    (net (code "59") (name "Net-(LED1-PadC)") (class "Default")
      (node (ref "LED1") (pin "C") (pinfunction "C_C") (pintype "passive"))
      (node (ref "R12") (pin "2") (pinfunction "2_2") (pintype "passive"))
    )
    (net (code "60") (name "Net-(LED2-PadC)") (class "Default")
      (node (ref "LED2") (pin "C") (pinfunction "C_C") (pintype "passive"))
      (node (ref "R13") (pin "2") (pinfunction "2_2") (pintype "passive"))
    )
    (net (code "61") (name "Net-(LED3-PadA)") (class "Default")
      (node (ref "LED3") (pin "A") (pinfunction "A_A") (pintype "passive"))
      (node (ref "R11") (pin "2") (pinfunction "2_2") (pintype "passive"))
    )
    (net (code "62") (name "Net-(LED4-PadA)") (class "Default")
      (node (ref "LED4") (pin "A") (pinfunction "A_A") (pintype "passive"))
      (node (ref "R7") (pin "2") (pinfunction "2_2") (pintype "passive"))
    )
    (net (code "63") (name "Net-(R1-Pad1)") (class "Default")
      (node (ref "R1") (pin "1") (pinfunction "1_1") (pintype "passive"))
      (node (ref "X1") (pin "3") (pinfunction "3_3") (pintype "passive"))
    )
    (net (code "64") (name "Net-(R2-Pad1)") (class "Default")
      (node (ref "R2") (pin "1") (pinfunction "1_1") (pintype "passive"))
      (node (ref "X1") (pin "2") (pinfunction "2_2") (pintype "passive"))
    )
    (net (code "65") (name "Net-(R3-Pad1)") (class "Default")
      (node (ref "R3") (pin "1") (pinfunction "1_1") (pintype "passive"))
      (node (ref "TRS1") (pin "5") (pinfunction "5_5") (pintype "bidirectional"))
    )
    (net (code "66") (name "Net-(R4-Pad1)") (class "Default")
      (node (ref "R4") (pin "1") (pinfunction "1_1") (pintype "passive"))
      (node (ref "TRS1") (pin "2") (pinfunction "2_2") (pintype "bidirectional"))
    )
    (net (code "67") (name "Net-(R5-Pad1)") (class "Default")
      (node (ref "R5") (pin "1") (pinfunction "1_1") (pintype "passive"))
      (node (ref "SWD") (pin "4") (pinfunction "4_4") (pintype "passive"))
    )
    (net (code "68") (name "Net-(R16-Pad2)") (class "Default")
      (node (ref "R16") (pin "2") (pinfunction "2_2") (pintype "passive"))
      (node (ref "R19") (pin "1") (pinfunction "1_1") (pintype "passive"))
    )
    (net (code "69") (name "Net-(SW1A-B)") (class "Default")
      (node (ref "ESP") (pin "3") (pinfunction "3_3") (pintype "passive"))
      (node (ref "SW1") (pin "B1") (pinfunction "B_B1") (pintype "bidirectional"))
    )
    (net (code "70") (name "Net-(SW1A-C)") (class "Default")
      (node (ref "SW1") (pin "C1") (pinfunction "C_C1") (pintype "bidirectional"))
      (node (ref "WIFI") (pin "22") (pinfunction "TXD_22") (pintype "bidirectional"))
    )
    (net (code "71") (name "Net-(SW1B-B)") (class "Default")
      (node (ref "ESP") (pin "2") (pinfunction "2_2") (pintype "passive"))
      (node (ref "SW1") (pin "B2") (pinfunction "B_B2") (pintype "bidirectional"))
    )
    (net (code "72") (name "Net-(SW1B-C)") (class "Default")
      (node (ref "SW1") (pin "C2") (pinfunction "C_C2") (pintype "bidirectional"))
      (node (ref "WIFI") (pin "21") (pinfunction "RXD_21") (pintype "bidirectional"))
    )
    (net (code "73") (name "Net-(T1-1)") (class "Default")
      (node (ref "D3") (pin "A") (pinfunction "A_A") (pintype "passive"))
      (node (ref "T1") (pin "P$1") (pinfunction "1_P$1") (pintype "passive"))
    )
    (net (code "74") (name "Net-(WIFI-GPIO4)") (class "Default")
      (node (ref "R7") (pin "1") (pinfunction "1_1") (pintype "passive"))
      (node (ref "WIFI") (pin "19") (pinfunction "GPIO4_19") (pintype "bidirectional"))
    )
    (net (code "75") (name "Net-(WIFI-GPIO5)") (class "Default")
      (node (ref "R11") (pin "1") (pinfunction "1_1") (pintype "passive"))
      (node (ref "WIFI") (pin "20") (pinfunction "GPIO5_20") (pintype "bidirectional"))
    )
    (net (code "76") (name "Net-(WIFI-GPIO15)") (class "Default")
      (node (ref "R14") (pin "1") (pinfunction "1_1") (pintype "passive"))
      (node (ref "WIFI") (pin "16") (pinfunction "GPIO15_16") (pintype "bidirectional"))
    )
    (net (code "77") (name "unconnected-(IC1A-PA8-Pad29)") (class "Default")
      (node (ref "IC1") (pin "29") (pinfunction "PA8_29") (pintype "bidirectional"))
    )
    (net (code "78") (name "unconnected-(IC1A-PB5-Pad41)") (class "Default")
      (node (ref "IC1") (pin "41") (pinfunction "PB5_41") (pintype "bidirectional"))
    )
    (net (code "79") (name "unconnected-(IC1A-PB12-Pad25)") (class "Default")
      (node (ref "IC1") (pin "25") (pinfunction "PB12_25") (pintype "bidirectional"))
    )
    (net (code "80") (name "unconnected-(WIFI-ADC-Pad2)") (class "Default")
      (node (ref "WIFI") (pin "2") (pinfunction "ADC_2") (pintype "bidirectional"))
    )
    (net (code "81") (name "unconnected-(WIFI-CS0-Pad9)") (class "Default")
      (node (ref "WIFI") (pin "9") (pinfunction "CS0_9") (pintype "bidirectional"))
    )
    (net (code "82") (name "unconnected-(WIFI-GPIO2-Pad17)") (class "Default")
      (node (ref "WIFI") (pin "17") (pinfunction "GPIO2_17") (pintype "bidirectional"))
    )
    (net (code "83") (name "unconnected-(WIFI-GPIO12-Pad6)") (class "Default")
      (node (ref "WIFI") (pin "6") (pinfunction "GPIO12_6") (pintype "bidirectional"))
    )
    (net (code "84") (name "unconnected-(WIFI-GPIO13-Pad7)") (class "Default")
      (node (ref "WIFI") (pin "7") (pinfunction "GPIO13_7") (pintype "bidirectional"))
    )
    (net (code "85") (name "unconnected-(WIFI-GPIO14-Pad5)") (class "Default")
      (node (ref "WIFI") (pin "5") (pinfunction "GPIO14_5") (pintype "bidirectional"))
    )
    (net (code "86") (name "unconnected-(WIFI-GPIO16-Pad4)") (class "Default")
      (node (ref "WIFI") (pin "4") (pinfunction "GPIO16_4") (pintype "bidirectional"))
    )
    (net (code "87") (name "unconnected-(WIFI-IO9-Pad11)") (class "Default")
      (node (ref "WIFI") (pin "11") (pinfunction "IO9_11") (pintype "bidirectional"))
    )
    (net (code "88") (name "unconnected-(WIFI-IO10-Pad12)") (class "Default")
      (node (ref "WIFI") (pin "12") (pinfunction "IO10_12") (pintype "bidirectional"))
    )
    (net (code "89") (name "unconnected-(WIFI-MISO-Pad10)") (class "Default")
      (node (ref "WIFI") (pin "10") (pinfunction "MISO_10") (pintype "bidirectional"))
    )
    (net (code "90") (name "unconnected-(WIFI-MOSI-Pad13)") (class "Default")
      (node (ref "WIFI") (pin "13") (pinfunction "MOSI_13") (pintype "bidirectional"))
    )
    (net (code "91") (name "unconnected-(WIFI-SCLK-Pad14)") (class "Default")
      (node (ref "WIFI") (pin "14") (pinfunction "SCLK_14") (pintype "bidirectional"))
    )
    (net (code "92") (name "unconnected-(X1-Pad4)") (class "Default")
      (node (ref "X1") (pin "4") (pinfunction "4_4") (pintype "passive"))
    )
  )
)
